# Inyector_fibra_fusibles.net
KiCad netlist of a schematic drawn in EAGLE
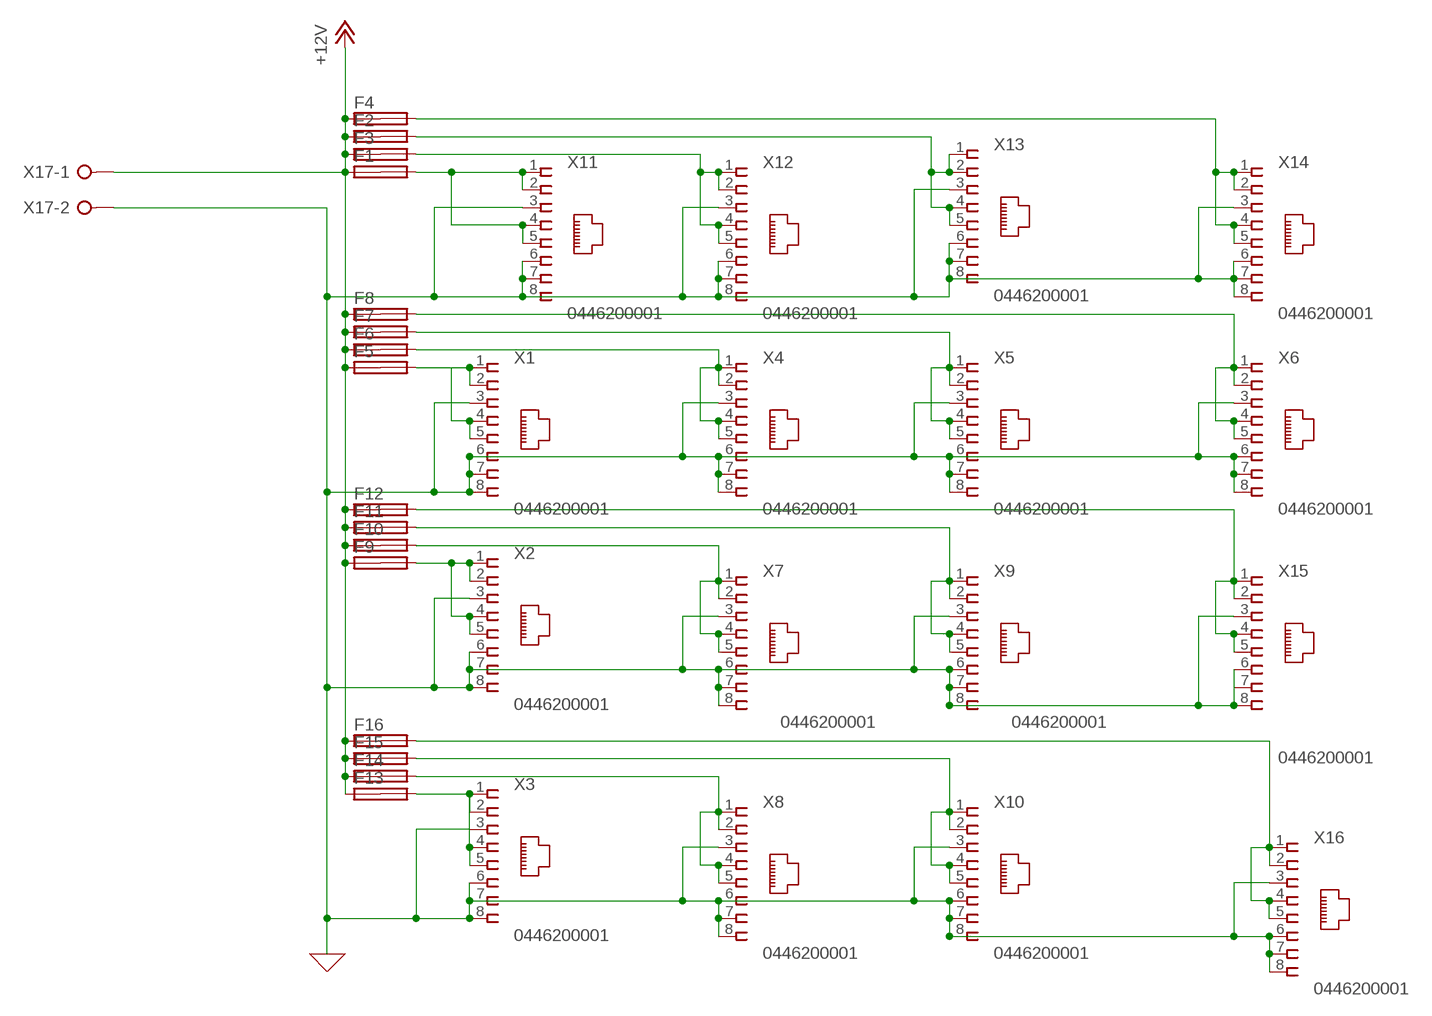
[diagram p0: schematic, sheet 1]

(export (version "E")
  (design (tool "Eeschema 10.0.6"))
  (components
    (comp (ref "F1")
      (value "SHK20Q")
      (footprint "eagle-import:SHK20Q")
      (libsource (lib "eagle-import") (part "SHK20Q"))
    )
    (comp (ref "F2")
      (value "SHK20Q")
      (footprint "eagle-import:SHK20Q")
      (libsource (lib "eagle-import") (part "SHK20Q"))
    )
    (comp (ref "F3")
      (value "SHK20Q")
      (footprint "eagle-import:SHK20Q")
      (libsource (lib "eagle-import") (part "SHK20Q"))
    )
    (comp (ref "F4")
      (value "SHK20Q")
      (footprint "eagle-import:SHK20Q")
      (libsource (lib "eagle-import") (part "SHK20Q"))
    )
    (comp (ref "F5")
      (value "SHK20Q")
      (footprint "eagle-import:SHK20Q")
      (libsource (lib "eagle-import") (part "SHK20Q"))
    )
    (comp (ref "F6")
      (value "SHK20Q")
      (footprint "eagle-import:SHK20Q")
      (libsource (lib "eagle-import") (part "SHK20Q"))
    )
    (comp (ref "F7")
      (value "SHK20Q")
      (footprint "eagle-import:SHK20Q")
      (libsource (lib "eagle-import") (part "SHK20Q"))
    )
    (comp (ref "F8")
      (value "SHK20Q")
      (footprint "eagle-import:SHK20Q")
      (libsource (lib "eagle-import") (part "SHK20Q"))
    )
    (comp (ref "F9")
      (value "SHK20Q")
      (footprint "eagle-import:SHK20Q")
      (libsource (lib "eagle-import") (part "SHK20Q"))
    )
    (comp (ref "F10")
      (value "SHK20Q")
      (footprint "eagle-import:SHK20Q")
      (libsource (lib "eagle-import") (part "SHK20Q"))
    )
    (comp (ref "F11")
      (value "SHK20Q")
      (footprint "eagle-import:SHK20Q")
      (libsource (lib "eagle-import") (part "SHK20Q"))
    )
    (comp (ref "F12")
      (value "SHK20Q")
      (footprint "eagle-import:SHK20Q")
      (libsource (lib "eagle-import") (part "SHK20Q"))
    )
    (comp (ref "F13")
      (value "SHK20Q")
      (footprint "eagle-import:SHK20Q")
      (libsource (lib "eagle-import") (part "SHK20Q"))
    )
    (comp (ref "F14")
      (value "SHK20Q")
      (footprint "eagle-import:SHK20Q")
      (libsource (lib "eagle-import") (part "SHK20Q"))
    )
    (comp (ref "F15")
      (value "SHK20Q")
      (footprint "eagle-import:SHK20Q")
      (libsource (lib "eagle-import") (part "SHK20Q"))
    )
    (comp (ref "F16")
      (value "SHK20Q")
      (footprint "eagle-import:SHK20Q")
      (libsource (lib "eagle-import") (part "SHK20Q"))
    )
    (comp (ref "X1")
      (value "0446200001")
      (footprint "eagle-import:0446200001")
      (fields (field (name "MF") "MOLEX"))
      (libsource (lib "eagle-import") (part "0446200001"))
    )
    (comp (ref "X2")
      (value "0446200001")
      (footprint "eagle-import:0446200001")
      (fields (field (name "MF") "MOLEX"))
      (libsource (lib "eagle-import") (part "0446200001"))
    )
    (comp (ref "X3")
      (value "0446200001")
      (footprint "eagle-import:0446200001")
      (fields (field (name "MF") "MOLEX"))
      (libsource (lib "eagle-import") (part "0446200001"))
    )
    (comp (ref "X4")
      (value "0446200001")
      (footprint "eagle-import:0446200001")
      (fields (field (name "MF") "MOLEX"))
      (libsource (lib "eagle-import") (part "0446200001"))
    )
    (comp (ref "X5")
      (value "0446200001")
      (footprint "eagle-import:0446200001")
      (fields (field (name "MF") "MOLEX"))
      (libsource (lib "eagle-import") (part "0446200001"))
    )
    (comp (ref "X6")
      (value "0446200001")
      (footprint "eagle-import:0446200001")
      (fields (field (name "MF") "MOLEX"))
      (libsource (lib "eagle-import") (part "0446200001"))
    )
    (comp (ref "X7")
      (value "0446200001")
      (footprint "eagle-import:0446200001")
      (fields (field (name "MF") "MOLEX"))
      (libsource (lib "eagle-import") (part "0446200001"))
    )
    (comp (ref "X8")
      (value "0446200001")
      (footprint "eagle-import:0446200001")
      (fields (field (name "MF") "MOLEX"))
      (libsource (lib "eagle-import") (part "0446200001"))
    )
    (comp (ref "X9")
      (value "0446200001")
      (footprint "eagle-import:0446200001")
      (fields (field (name "MF") "MOLEX"))
      (libsource (lib "eagle-import") (part "0446200001"))
    )
    (comp (ref "X10")
      (value "0446200001")
      (footprint "eagle-import:0446200001")
      (fields (field (name "MF") "MOLEX"))
      (libsource (lib "eagle-import") (part "0446200001"))
    )
    (comp (ref "X11")
      (value "0446200001")
      (footprint "eagle-import:0446200001")
      (fields (field (name "MF") "MOLEX"))
      (libsource (lib "eagle-import") (part "0446200001"))
    )
    (comp (ref "X12")
      (value "0446200001")
      (footprint "eagle-import:0446200001")
      (fields (field (name "MF") "MOLEX"))
      (libsource (lib "eagle-import") (part "0446200001"))
    )
    (comp (ref "X13")
      (value "0446200001")
      (footprint "eagle-import:0446200001")
      (fields (field (name "MF") "MOLEX"))
      (libsource (lib "eagle-import") (part "0446200001"))
    )
    (comp (ref "X14")
      (value "0446200001")
      (footprint "eagle-import:0446200001")
      (fields (field (name "MF") "MOLEX"))
      (libsource (lib "eagle-import") (part "0446200001"))
    )
    (comp (ref "X15")
      (value "0446200001")
      (footprint "eagle-import:0446200001")
      (fields (field (name "MF") "MOLEX"))
      (libsource (lib "eagle-import") (part "0446200001"))
    )
    (comp (ref "X16")
      (value "0446200001")
      (footprint "eagle-import:0446200001")
      (fields (field (name "MF") "MOLEX"))
      (libsource (lib "eagle-import") (part "0446200001"))
    )
    (comp (ref "X17")
      (value "W237-02P")
      (footprint "eagle-import:W237-132")
      (libsource (lib "eagle-import") (part "W237-02P"))
    )
  )
  (nets
    (net (code "1") (name "+12V") (class "Default")
      (node (ref "F1") (pin "1A") (pinfunction "1A_1A") (pintype "passive"))
      (node (ref "F10") (pin "1A") (pinfunction "1A_1A") (pintype "passive"))
      (node (ref "F11") (pin "1A") (pinfunction "1A_1A") (pintype "passive"))
      (node (ref "F12") (pin "1A") (pinfunction "1A_1A") (pintype "passive"))
      (node (ref "F13") (pin "1A") (pinfunction "1A_1A") (pintype "passive"))
      (node (ref "F14") (pin "1A") (pinfunction "1A_1A") (pintype "passive"))
      (node (ref "F15") (pin "1A") (pinfunction "1A_1A") (pintype "passive"))
      (node (ref "F16") (pin "1A") (pinfunction "1A_1A") (pintype "passive"))
      (node (ref "F2") (pin "1A") (pinfunction "1A_1A") (pintype "passive"))
      (node (ref "F3") (pin "1A") (pinfunction "1A_1A") (pintype "passive"))
      (node (ref "F4") (pin "1A") (pinfunction "1A_1A") (pintype "passive"))
      (node (ref "F5") (pin "1A") (pinfunction "1A_1A") (pintype "passive"))
      (node (ref "F6") (pin "1A") (pinfunction "1A_1A") (pintype "passive"))
      (node (ref "F7") (pin "1A") (pinfunction "1A_1A") (pintype "passive"))
      (node (ref "F8") (pin "1A") (pinfunction "1A_1A") (pintype "passive"))
      (node (ref "F9") (pin "1A") (pinfunction "1A_1A") (pintype "passive"))
      (node (ref "X17") (pin "1") (pinfunction "KL_1") (pintype "passive"))
    )
    (net (code "2") (name "GND") (class "Default")
      (node (ref "X1") (pin "3") (pinfunction "3_3") (pintype "passive"))
      (node (ref "X1") (pin "6") (pinfunction "6_6") (pintype "passive"))
      (node (ref "X1") (pin "7") (pinfunction "7_7") (pintype "passive"))
      (node (ref "X1") (pin "8") (pinfunction "8_8") (pintype "passive"))
      (node (ref "X10") (pin "3") (pinfunction "3_3") (pintype "passive"))
      (node (ref "X10") (pin "6") (pinfunction "6_6") (pintype "passive"))
      (node (ref "X10") (pin "7") (pinfunction "7_7") (pintype "passive"))
      (node (ref "X10") (pin "8") (pinfunction "8_8") (pintype "passive"))
      (node (ref "X11") (pin "3") (pinfunction "3_3") (pintype "passive"))
      (node (ref "X11") (pin "6") (pinfunction "6_6") (pintype "passive"))
      (node (ref "X11") (pin "7") (pinfunction "7_7") (pintype "passive"))
      (node (ref "X11") (pin "8") (pinfunction "8_8") (pintype "passive"))
      (node (ref "X12") (pin "3") (pinfunction "3_3") (pintype "passive"))
      (node (ref "X12") (pin "6") (pinfunction "6_6") (pintype "passive"))
      (node (ref "X12") (pin "7") (pinfunction "7_7") (pintype "passive"))
      (node (ref "X12") (pin "8") (pinfunction "8_8") (pintype "passive"))
      (node (ref "X13") (pin "3") (pinfunction "3_3") (pintype "passive"))
      (node (ref "X13") (pin "6") (pinfunction "6_6") (pintype "passive"))
      (node (ref "X13") (pin "7") (pinfunction "7_7") (pintype "passive"))
      (node (ref "X13") (pin "8") (pinfunction "8_8") (pintype "passive"))
      (node (ref "X14") (pin "3") (pinfunction "3_3") (pintype "passive"))
      (node (ref "X14") (pin "6") (pinfunction "6_6") (pintype "passive"))
      (node (ref "X14") (pin "7") (pinfunction "7_7") (pintype "passive"))
      (node (ref "X14") (pin "8") (pinfunction "8_8") (pintype "passive"))
      (node (ref "X15") (pin "3") (pinfunction "3_3") (pintype "passive"))
      (node (ref "X15") (pin "6") (pinfunction "6_6") (pintype "passive"))
      (node (ref "X15") (pin "7") (pinfunction "7_7") (pintype "passive"))
      (node (ref "X15") (pin "8") (pinfunction "8_8") (pintype "passive"))
      (node (ref "X16") (pin "3") (pinfunction "3_3") (pintype "passive"))
      (node (ref "X16") (pin "6") (pinfunction "6_6") (pintype "passive"))
      (node (ref "X16") (pin "7") (pinfunction "7_7") (pintype "passive"))
      (node (ref "X16") (pin "8") (pinfunction "8_8") (pintype "passive"))
      (node (ref "X17") (pin "2") (pinfunction "KL_2") (pintype "passive"))
      (node (ref "X2") (pin "3") (pinfunction "3_3") (pintype "passive"))
      (node (ref "X2") (pin "6") (pinfunction "6_6") (pintype "passive"))
      (node (ref "X2") (pin "7") (pinfunction "7_7") (pintype "passive"))
      (node (ref "X2") (pin "8") (pinfunction "8_8") (pintype "passive"))
      (node (ref "X3") (pin "3") (pinfunction "3_3") (pintype "passive"))
      (node (ref "X3") (pin "6") (pinfunction "6_6") (pintype "passive"))
      (node (ref "X3") (pin "7") (pinfunction "7_7") (pintype "passive"))
      (node (ref "X3") (pin "8") (pinfunction "8_8") (pintype "passive"))
      (node (ref "X4") (pin "3") (pinfunction "3_3") (pintype "passive"))
      (node (ref "X4") (pin "6") (pinfunction "6_6") (pintype "passive"))
      (node (ref "X4") (pin "7") (pinfunction "7_7") (pintype "passive"))
      (node (ref "X4") (pin "8") (pinfunction "8_8") (pintype "passive"))
      (node (ref "X5") (pin "3") (pinfunction "3_3") (pintype "passive"))
      (node (ref "X5") (pin "6") (pinfunction "6_6") (pintype "passive"))
      (node (ref "X5") (pin "7") (pinfunction "7_7") (pintype "passive"))
      (node (ref "X5") (pin "8") (pinfunction "8_8") (pintype "passive"))
      (node (ref "X6") (pin "3") (pinfunction "3_3") (pintype "passive"))
      (node (ref "X6") (pin "6") (pinfunction "6_6") (pintype "passive"))
      (node (ref "X6") (pin "7") (pinfunction "7_7") (pintype "passive"))
      (node (ref "X6") (pin "8") (pinfunction "8_8") (pintype "passive"))
      (node (ref "X7") (pin "3") (pinfunction "3_3") (pintype "passive"))
      (node (ref "X7") (pin "6") (pinfunction "6_6") (pintype "passive"))
      (node (ref "X7") (pin "7") (pinfunction "7_7") (pintype "passive"))
      (node (ref "X7") (pin "8") (pinfunction "8_8") (pintype "passive"))
      (node (ref "X8") (pin "3") (pinfunction "3_3") (pintype "passive"))
      (node (ref "X8") (pin "6") (pinfunction "6_6") (pintype "passive"))
      (node (ref "X8") (pin "7") (pinfunction "7_7") (pintype "passive"))
      (node (ref "X8") (pin "8") (pinfunction "8_8") (pintype "passive"))
      (node (ref "X9") (pin "3") (pinfunction "3_3") (pintype "passive"))
      (node (ref "X9") (pin "6") (pinfunction "6_6") (pintype "passive"))
      (node (ref "X9") (pin "7") (pinfunction "7_7") (pintype "passive"))
      (node (ref "X9") (pin "8") (pinfunction "8_8") (pintype "passive"))
    )
    (net (code "3") (name "Net-(F1-Pad2A)") (class "Default")
      (node (ref "F1") (pin "2A") (pinfunction "2A_2A") (pintype "passive"))
      (node (ref "X11") (pin "1") (pinfunction "1_1") (pintype "passive"))
      (node (ref "X11") (pin "2") (pinfunction "2_2") (pintype "passive"))
      (node (ref "X11") (pin "4") (pinfunction "4_4") (pintype "passive"))
      (node (ref "X11") (pin "5") (pinfunction "5_5") (pintype "passive"))
    )
    (net (code "4") (name "Net-(F2-Pad2A)") (class "Default")
      (node (ref "F2") (pin "2A") (pinfunction "2A_2A") (pintype "passive"))
      (node (ref "X13") (pin "1") (pinfunction "1_1") (pintype "passive"))
      (node (ref "X13") (pin "2") (pinfunction "2_2") (pintype "passive"))
      (node (ref "X13") (pin "4") (pinfunction "4_4") (pintype "passive"))
      (node (ref "X13") (pin "5") (pinfunction "5_5") (pintype "passive"))
    )
    (net (code "5") (name "Net-(F3-Pad2A)") (class "Default")
      (node (ref "F3") (pin "2A") (pinfunction "2A_2A") (pintype "passive"))
      (node (ref "X12") (pin "1") (pinfunction "1_1") (pintype "passive"))
      (node (ref "X12") (pin "2") (pinfunction "2_2") (pintype "passive"))
      (node (ref "X12") (pin "4") (pinfunction "4_4") (pintype "passive"))
      (node (ref "X12") (pin "5") (pinfunction "5_5") (pintype "passive"))
    )
    (net (code "6") (name "Net-(F4-Pad2A)") (class "Default")
      (node (ref "F4") (pin "2A") (pinfunction "2A_2A") (pintype "passive"))
      (node (ref "X14") (pin "1") (pinfunction "1_1") (pintype "passive"))
      (node (ref "X14") (pin "2") (pinfunction "2_2") (pintype "passive"))
      (node (ref "X14") (pin "4") (pinfunction "4_4") (pintype "passive"))
      (node (ref "X14") (pin "5") (pinfunction "5_5") (pintype "passive"))
    )
    (net (code "7") (name "Net-(F5-Pad2A)") (class "Default")
      (node (ref "F5") (pin "2A") (pinfunction "2A_2A") (pintype "passive"))
      (node (ref "X1") (pin "1") (pinfunction "1_1") (pintype "passive"))
      (node (ref "X1") (pin "2") (pinfunction "2_2") (pintype "passive"))
      (node (ref "X1") (pin "4") (pinfunction "4_4") (pintype "passive"))
      (node (ref "X1") (pin "5") (pinfunction "5_5") (pintype "passive"))
    )
    (net (code "8") (name "Net-(F6-Pad2A)") (class "Default")
      (node (ref "F6") (pin "2A") (pinfunction "2A_2A") (pintype "passive"))
      (node (ref "X4") (pin "1") (pinfunction "1_1") (pintype "passive"))
      (node (ref "X4") (pin "2") (pinfunction "2_2") (pintype "passive"))
      (node (ref "X4") (pin "4") (pinfunction "4_4") (pintype "passive"))
      (node (ref "X4") (pin "5") (pinfunction "5_5") (pintype "passive"))
    )
    (net (code "9") (name "Net-(F7-Pad2A)") (class "Default")
      (node (ref "F7") (pin "2A") (pinfunction "2A_2A") (pintype "passive"))
      (node (ref "X5") (pin "1") (pinfunction "1_1") (pintype "passive"))
      (node (ref "X5") (pin "2") (pinfunction "2_2") (pintype "passive"))
      (node (ref "X5") (pin "4") (pinfunction "4_4") (pintype "passive"))
      (node (ref "X5") (pin "5") (pinfunction "5_5") (pintype "passive"))
    )
    (net (code "10") (name "Net-(F8-Pad2A)") (class "Default")
      (node (ref "F8") (pin "2A") (pinfunction "2A_2A") (pintype "passive"))
      (node (ref "X6") (pin "1") (pinfunction "1_1") (pintype "passive"))
      (node (ref "X6") (pin "2") (pinfunction "2_2") (pintype "passive"))
      (node (ref "X6") (pin "4") (pinfunction "4_4") (pintype "passive"))
      (node (ref "X6") (pin "5") (pinfunction "5_5") (pintype "passive"))
    )
    (net (code "11") (name "Net-(F9-Pad2A)") (class "Default")
      (node (ref "F9") (pin "2A") (pinfunction "2A_2A") (pintype "passive"))
      (node (ref "X2") (pin "1") (pinfunction "1_1") (pintype "passive"))
      (node (ref "X2") (pin "2") (pinfunction "2_2") (pintype "passive"))
      (node (ref "X2") (pin "4") (pinfunction "4_4") (pintype "passive"))
      (node (ref "X2") (pin "5") (pinfunction "5_5") (pintype "passive"))
    )
    (net (code "12") (name "Net-(F10-Pad2A)") (class "Default")
      (node (ref "F10") (pin "2A") (pinfunction "2A_2A") (pintype "passive"))
      (node (ref "X7") (pin "1") (pinfunction "1_1") (pintype "passive"))
      (node (ref "X7") (pin "2") (pinfunction "2_2") (pintype "passive"))
      (node (ref "X7") (pin "4") (pinfunction "4_4") (pintype "passive"))
      (node (ref "X7") (pin "5") (pinfunction "5_5") (pintype "passive"))
    )
    (net (code "13") (name "Net-(F11-Pad2A)") (class "Default")
      (node (ref "F11") (pin "2A") (pinfunction "2A_2A") (pintype "passive"))
      (node (ref "X9") (pin "1") (pinfunction "1_1") (pintype "passive"))
      (node (ref "X9") (pin "2") (pinfunction "2_2") (pintype "passive"))
      (node (ref "X9") (pin "4") (pinfunction "4_4") (pintype "passive"))
      (node (ref "X9") (pin "5") (pinfunction "5_5") (pintype "passive"))
    )
    (net (code "14") (name "Net-(F12-Pad2A)") (class "Default")
      (node (ref "F12") (pin "2A") (pinfunction "2A_2A") (pintype "passive"))
      (node (ref "X15") (pin "1") (pinfunction "1_1") (pintype "passive"))
      (node (ref "X15") (pin "2") (pinfunction "2_2") (pintype "passive"))
      (node (ref "X15") (pin "4") (pinfunction "4_4") (pintype "passive"))
      (node (ref "X15") (pin "5") (pinfunction "5_5") (pintype "passive"))
    )
    (net (code "15") (name "Net-(F13-Pad2A)") (class "Default")
      (node (ref "F13") (pin "2A") (pinfunction "2A_2A") (pintype "passive"))
      (node (ref "X3") (pin "1") (pinfunction "1_1") (pintype "passive"))
      (node (ref "X3") (pin "2") (pinfunction "2_2") (pintype "passive"))
      (node (ref "X3") (pin "4") (pinfunction "4_4") (pintype "passive"))
      (node (ref "X3") (pin "5") (pinfunction "5_5") (pintype "passive"))
    )
    (net (code "16") (name "Net-(F14-Pad2A)") (class "Default")
      (node (ref "F14") (pin "2A") (pinfunction "2A_2A") (pintype "passive"))
      (node (ref "X8") (pin "1") (pinfunction "1_1") (pintype "passive"))
      (node (ref "X8") (pin "2") (pinfunction "2_2") (pintype "passive"))
      (node (ref "X8") (pin "4") (pinfunction "4_4") (pintype "passive"))
      (node (ref "X8") (pin "5") (pinfunction "5_5") (pintype "passive"))
    )
    (net (code "17") (name "Net-(F15-Pad2A)") (class "Default")
      (node (ref "F15") (pin "2A") (pinfunction "2A_2A") (pintype "passive"))
      (node (ref "X10") (pin "1") (pinfunction "1_1") (pintype "passive"))
      (node (ref "X10") (pin "2") (pinfunction "2_2") (pintype "passive"))
      (node (ref "X10") (pin "4") (pinfunction "4_4") (pintype "passive"))
      (node (ref "X10") (pin "5") (pinfunction "5_5") (pintype "passive"))
    )
    (net (code "18") (name "Net-(F16-Pad2A)") (class "Default")
      (node (ref "F16") (pin "2A") (pinfunction "2A_2A") (pintype "passive"))
      (node (ref "X16") (pin "1") (pinfunction "1_1") (pintype "passive"))
      (node (ref "X16") (pin "2") (pinfunction "2_2") (pintype "passive"))
      (node (ref "X16") (pin "4") (pinfunction "4_4") (pintype "passive"))
      (node (ref "X16") (pin "5") (pinfunction "5_5") (pintype "passive"))
    )
    (net (code "19") (name "unconnected-(F1-Pad1B)") (class "Default")
      (node (ref "F1") (pin "1B") (pinfunction "1B_1B") (pintype "passive"))
    )
    (net (code "20") (name "unconnected-(F1-Pad2B)") (class "Default")
      (node (ref "F1") (pin "2B") (pinfunction "2B_2B") (pintype "passive"))
    )
    (net (code "21") (name "unconnected-(F2-Pad1B)") (class "Default")
      (node (ref "F2") (pin "1B") (pinfunction "1B_1B") (pintype "passive"))
    )
    (net (code "22") (name "unconnected-(F2-Pad2B)") (class "Default")
      (node (ref "F2") (pin "2B") (pinfunction "2B_2B") (pintype "passive"))
    )
    (net (code "23") (name "unconnected-(F3-Pad1B)") (class "Default")
      (node (ref "F3") (pin "1B") (pinfunction "1B_1B") (pintype "passive"))
    )
    (net (code "24") (name "unconnected-(F3-Pad2B)") (class "Default")
      (node (ref "F3") (pin "2B") (pinfunction "2B_2B") (pintype "passive"))
    )
    (net (code "25") (name "unconnected-(F4-Pad1B)") (class "Default")
      (node (ref "F4") (pin "1B") (pinfunction "1B_1B") (pintype "passive"))
    )
    (net (code "26") (name "unconnected-(F4-Pad2B)") (class "Default")
      (node (ref "F4") (pin "2B") (pinfunction "2B_2B") (pintype "passive"))
    )
    (net (code "27") (name "unconnected-(F5-Pad1B)") (class "Default")
      (node (ref "F5") (pin "1B") (pinfunction "1B_1B") (pintype "passive"))
    )
    (net (code "28") (name "unconnected-(F5-Pad2B)") (class "Default")
      (node (ref "F5") (pin "2B") (pinfunction "2B_2B") (pintype "passive"))
    )
    (net (code "29") (name "unconnected-(F6-Pad1B)") (class "Default")
      (node (ref "F6") (pin "1B") (pinfunction "1B_1B") (pintype "passive"))
    )
    (net (code "30") (name "unconnected-(F6-Pad2B)") (class "Default")
      (node (ref "F6") (pin "2B") (pinfunction "2B_2B") (pintype "passive"))
    )
    (net (code "31") (name "unconnected-(F7-Pad1B)") (class "Default")
      (node (ref "F7") (pin "1B") (pinfunction "1B_1B") (pintype "passive"))
    )
    (net (code "32") (name "unconnected-(F7-Pad2B)") (class "Default")
      (node (ref "F7") (pin "2B") (pinfunction "2B_2B") (pintype "passive"))
    )
    (net (code "33") (name "unconnected-(F8-Pad1B)") (class "Default")
      (node (ref "F8") (pin "1B") (pinfunction "1B_1B") (pintype "passive"))
    )
    (net (code "34") (name "unconnected-(F8-Pad2B)") (class "Default")
      (node (ref "F8") (pin "2B") (pinfunction "2B_2B") (pintype "passive"))
    )
    (net (code "35") (name "unconnected-(F9-Pad1B)") (class "Default")
      (node (ref "F9") (pin "1B") (pinfunction "1B_1B") (pintype "passive"))
    )
    (net (code "36") (name "unconnected-(F9-Pad2B)") (class "Default")
      (node (ref "F9") (pin "2B") (pinfunction "2B_2B") (pintype "passive"))
    )
    (net (code "37") (name "unconnected-(F10-Pad1B)") (class "Default")
      (node (ref "F10") (pin "1B") (pinfunction "1B_1B") (pintype "passive"))
    )
    (net (code "38") (name "unconnected-(F10-Pad2B)") (class "Default")
      (node (ref "F10") (pin "2B") (pinfunction "2B_2B") (pintype "passive"))
    )
    (net (code "39") (name "unconnected-(F11-Pad1B)") (class "Default")
      (node (ref "F11") (pin "1B") (pinfunction "1B_1B") (pintype "passive"))
    )
    (net (code "40") (name "unconnected-(F11-Pad2B)") (class "Default")
      (node (ref "F11") (pin "2B") (pinfunction "2B_2B") (pintype "passive"))
    )
    (net (code "41") (name "unconnected-(F12-Pad1B)") (class "Default")
      (node (ref "F12") (pin "1B") (pinfunction "1B_1B") (pintype "passive"))
    )
    (net (code "42") (name "unconnected-(F12-Pad2B)") (class "Default")
      (node (ref "F12") (pin "2B") (pinfunction "2B_2B") (pintype "passive"))
    )
    (net (code "43") (name "unconnected-(F13-Pad1B)") (class "Default")
      (node (ref "F13") (pin "1B") (pinfunction "1B_1B") (pintype "passive"))
    )
    (net (code "44") (name "unconnected-(F13-Pad2B)") (class "Default")
      (node (ref "F13") (pin "2B") (pinfunction "2B_2B") (pintype "passive"))
    )
    (net (code "45") (name "unconnected-(F14-Pad1B)") (class "Default")
      (node (ref "F14") (pin "1B") (pinfunction "1B_1B") (pintype "passive"))
    )
    (net (code "46") (name "unconnected-(F14-Pad2B)") (class "Default")
      (node (ref "F14") (pin "2B") (pinfunction "2B_2B") (pintype "passive"))
    )
    (net (code "47") (name "unconnected-(F15-Pad1B)") (class "Default")
      (node (ref "F15") (pin "1B") (pinfunction "1B_1B") (pintype "passive"))
    )
    (net (code "48") (name "unconnected-(F15-Pad2B)") (class "Default")
      (node (ref "F15") (pin "2B") (pinfunction "2B_2B") (pintype "passive"))
    )
    (net (code "49") (name "unconnected-(F16-Pad1B)") (class "Default")
      (node (ref "F16") (pin "1B") (pinfunction "1B_1B") (pintype "passive"))
    )
    (net (code "50") (name "unconnected-(F16-Pad2B)") (class "Default")
      (node (ref "F16") (pin "2B") (pinfunction "2B_2B") (pintype "passive"))
    )
  )
)
